# ProPrj_TweenWave_2025-12-02.net
KiCad netlist of a schematic drawn in EasyEDA Pro
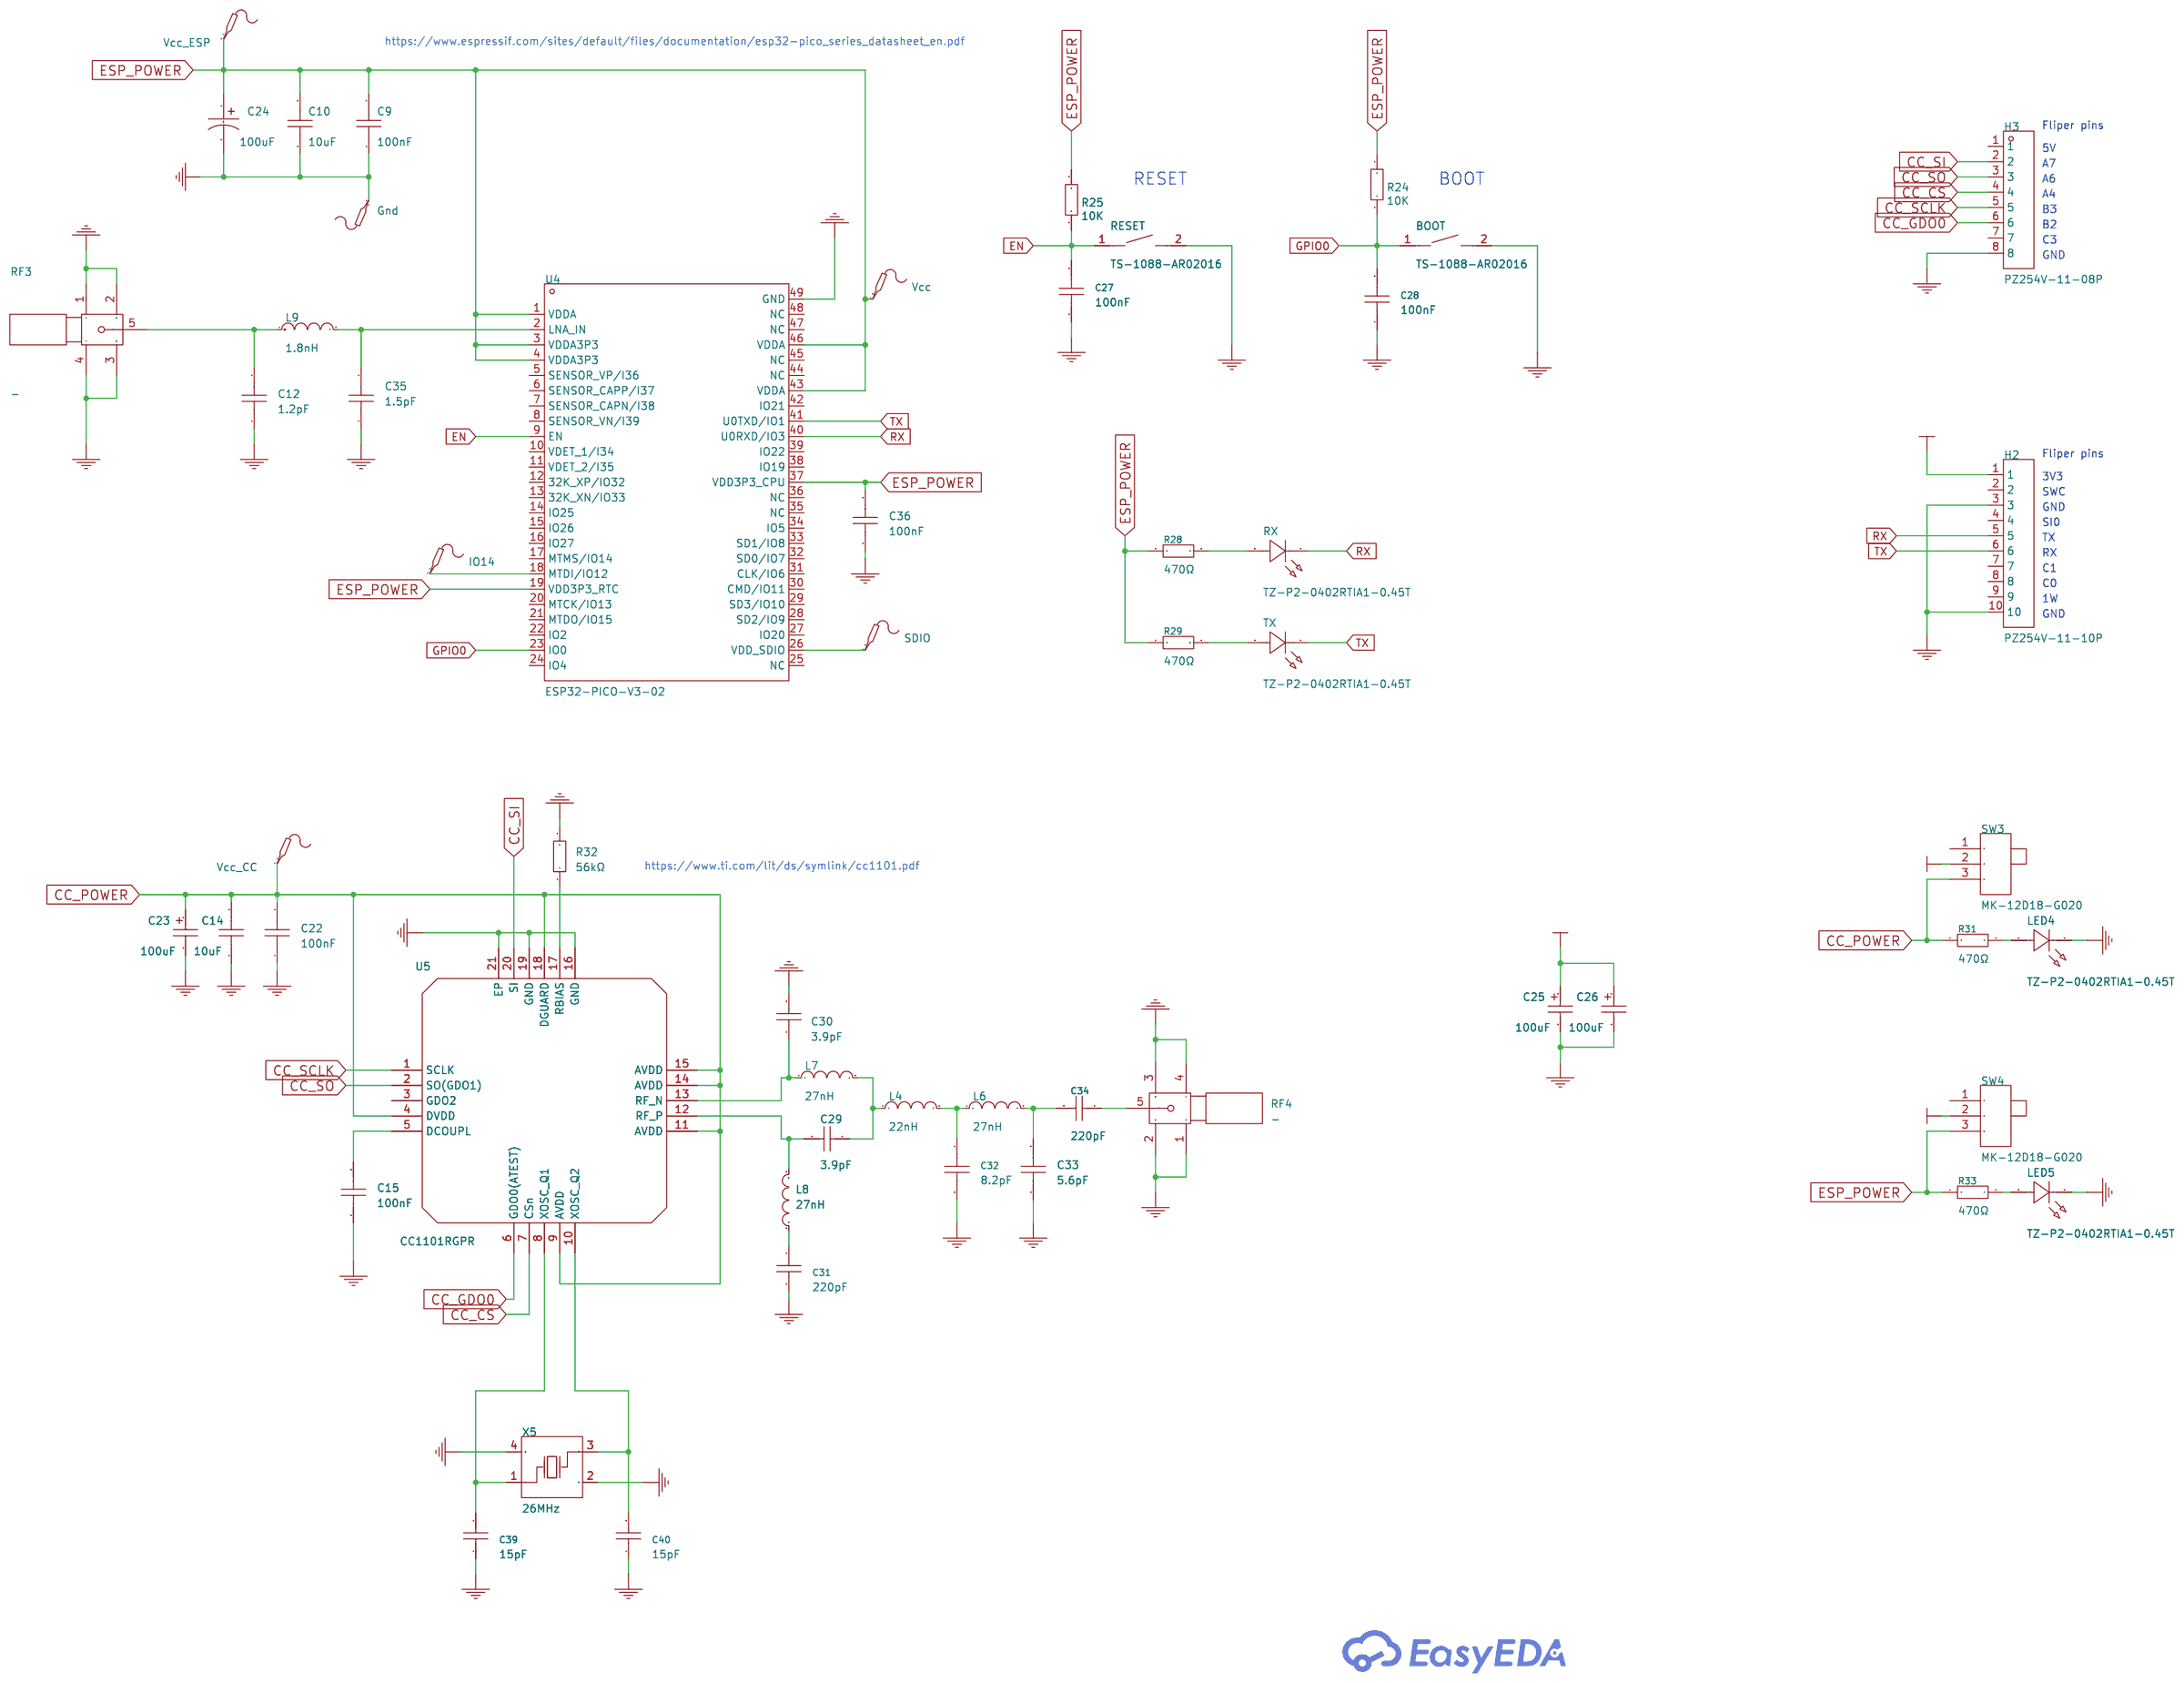
[diagram p0: schematic sheet]

(export (version "E")
  (design (tool "Eeschema 10.0.6"))
  (components
    (comp (ref "BOOT")
      (value "TS-1088-AR02016")
      (footprint "easyedapro:SW-SMD_L3.9-W3.0-P4.45")
      (fields (field (name "Manufacturer") "XUNPU(讯普)"))
      (libsource (lib "easyedapro") (part "TS-1088-AR02016"))
    )
    (comp (ref "C9")
      (value "100nF")
      (footprint "easyedapro:C0603")
      (description "Capacitance:100nF Tolerance:±10% Tolerance:±10% Voltage Rating:50V Temperature Coefficient:X7R")
      (fields
        (field (name "Manufacturer Part") "CC0603KRX7R9BB104")
        (field (name "Manufacturer") "YAGEO(国巨)")
      )
      (libsource (lib "easyedapro") (part "CC0603KRX7R9BB104"))
    )
    (comp (ref "C10")
      (value "10uF")
      (footprint "easyedapro:C0603")
      (fields
        (field (name "Manufacturer Part") "CL10A106MP8NNNC")
        (field (name "Manufacturer") "SAMSUNG(三星)")
      )
      (libsource (lib "easyedapro") (part "CL10A106MP8NNNC"))
    )
    (comp (ref "C12")
      (value "1.2pF")
      (footprint "easyedapro:C0201")
      (fields
        (field (name "Manufacturer Part") "GRM0335C1H1R2BA01D")
        (field (name "Manufacturer") "muRata(村田)")
      )
      (libsource (lib "easyedapro") (part "GRM0335C1H1R2BA01D"))
    )
    (comp (ref "C14")
      (value "10uF")
      (footprint "easyedapro:C0603")
      (fields
        (field (name "Manufacturer Part") "CL10A106MP8NNNC")
        (field (name "Manufacturer") "SAMSUNG(三星)")
      )
      (libsource (lib "easyedapro") (part "CL10A106MP8NNNC"))
    )
    (comp (ref "C15")
      (value "100nF")
      (footprint "easyedapro:C0603")
      (description "Capacitance:100nF Tolerance:±10% Tolerance:±10% Voltage Rating:50V Temperature Coefficient:X7R")
      (fields
        (field (name "Manufacturer Part") "CC0603KRX7R9BB104")
        (field (name "Manufacturer") "YAGEO(国巨)")
      )
      (libsource (lib "easyedapro") (part "CC0603KRX7R9BB104"))
    )
    (comp (ref "C22")
      (value "100nF")
      (footprint "easyedapro:C0603")
      (description "Capacitance:100nF Tolerance:±10% Tolerance:±10% Voltage Rating:50V Temperature Coefficient:X7R")
      (fields
        (field (name "Manufacturer Part") "CC0603KRX7R9BB104")
        (field (name "Manufacturer") "YAGEO(国巨)")
      )
      (libsource (lib "easyedapro") (part "CC0603KRX7R9BB104"))
    )
    (comp (ref "C23")
      (value "100uF")
      (footprint "easyedapro:CASE-B_3528")
      (fields (field (name "Manufacturer Part") "TAJB107K006RNJ") (field (name "Manufacturer") "Kyocera AVX"))
      (libsource (lib "easyedapro") (part "TAJB107K006RNJ"))
    )
    (comp (ref "C24")
      (value "100uF")
      (footprint "easyedapro:CASE-B_3528-1")
      (fields
        (field (name "Manufacturer Part") "TPSB107K006R0250")
        (field (name "Manufacturer") "Kyocera AVX")
      )
      (libsource (lib "easyedapro") (part "TPSB107K006R0250"))
    )
    (comp (ref "C25")
      (value "100uF")
      (footprint "easyedapro:CASE-B_3528")
      (fields (field (name "Manufacturer Part") "TAJB107K006RNJ") (field (name "Manufacturer") "Kyocera AVX"))
      (libsource (lib "easyedapro") (part "TAJB107K006RNJ"))
    )
    (comp (ref "C26")
      (value "100uF")
      (footprint "easyedapro:CASE-B_3528")
      (fields (field (name "Manufacturer Part") "TAJB107K006RNJ") (field (name "Manufacturer") "Kyocera AVX"))
      (libsource (lib "easyedapro") (part "TAJB107K006RNJ"))
    )
    (comp (ref "C27")
      (value "100nF")
      (footprint "easyedapro:C0402")
      (fields
        (field (name "Manufacturer Part") "CC0402KRX7R7BB104")
        (field (name "Manufacturer") "YAGEO(国巨)")
      )
      (libsource (lib "easyedapro") (part "CC0402KRX7R7BB104"))
    )
    (comp (ref "C28")
      (value "100nF")
      (footprint "easyedapro:C0402")
      (fields
        (field (name "Manufacturer Part") "CC0402KRX7R7BB104")
        (field (name "Manufacturer") "YAGEO(国巨)")
      )
      (libsource (lib "easyedapro") (part "CC0402KRX7R7BB104"))
    )
    (comp (ref "C29")
      (value "3.9pF")
      (footprint "easyedapro:C0402")
      (fields (field (name "Manufacturer Part") "0402CG3R9C500NT") (field (name "Manufacturer") "FH(风华)"))
      (libsource (lib "easyedapro") (part "0402CG3R9C500NT"))
    )
    (comp (ref "C30")
      (value "3.9pF")
      (footprint "easyedapro:C0402")
      (fields (field (name "Manufacturer Part") "0402CG3R9C500NT") (field (name "Manufacturer") "FH(风华)"))
      (libsource (lib "easyedapro") (part "0402CG3R9C500NT"))
    )
    (comp (ref "C31")
      (value "220pF")
      (footprint "easyedapro:C0402")
      (description "Capacitance:220pF Tolerance:±5% Tolerance:±5% Voltage Rating:50V Temperature Coefficient:NP0")
      (fields
        (field (name "Manufacturer Part") "CC0402JRNPO9BN221")
        (field (name "Manufacturer") "YAGEO(国巨)")
      )
      (libsource (lib "easyedapro") (part "CC0402JRNPO9BN221"))
    )
    (comp (ref "C32")
      (value "8.2pF")
      (footprint "easyedapro:C0402")
      (fields
        (field (name "Manufacturer Part") "CC0402BRNPO9BN8R2")
        (field (name "Manufacturer") "YAGEO(国巨)")
      )
      (libsource (lib "easyedapro") (part "CC0402BRNPO9BN8R2"))
    )
    (comp (ref "C33")
      (value "5.6pF")
      (footprint "easyedapro:C0402")
      (fields
        (field (name "Manufacturer Part") "CC0402BRNPO9BN5R6")
        (field (name "Manufacturer") "YAGEO(国巨)")
      )
      (libsource (lib "easyedapro") (part "CC0402BRNPO9BN5R6"))
    )
    (comp (ref "C34")
      (value "220pF")
      (footprint "easyedapro:C0402")
      (description "Capacitance:220pF Tolerance:±5% Tolerance:±5% Voltage Rating:50V Temperature Coefficient:NP0")
      (fields
        (field (name "Manufacturer Part") "CC0402JRNPO9BN221")
        (field (name "Manufacturer") "YAGEO(国巨)")
      )
      (libsource (lib "easyedapro") (part "CC0402JRNPO9BN221"))
    )
    (comp (ref "C35")
      (value "1.5pF")
      (footprint "easyedapro:C0201")
      (fields
        (field (name "Manufacturer Part") "GRM0335C1H1R5BA01D")
        (field (name "Manufacturer") "muRata(村田)")
      )
      (libsource (lib "easyedapro") (part "GRM0335C1H1R5BA01D"))
    )
    (comp (ref "C36")
      (value "100nF")
      (footprint "easyedapro:C0603")
      (description "Capacitance:100nF Tolerance:±10% Tolerance:±10% Voltage Rating:50V Temperature Coefficient:X7R")
      (fields
        (field (name "Manufacturer Part") "CC0603KRX7R9BB104")
        (field (name "Manufacturer") "YAGEO(国巨)")
      )
      (libsource (lib "easyedapro") (part "CC0603KRX7R9BB104"))
    )
    (comp (ref "C39")
      (value "15pF")
      (footprint "easyedapro:C0402")
      (fields
        (field (name "Manufacturer Part") "CC0402JRNPO9BN150")
        (field (name "Manufacturer") "YAGEO(国巨)")
      )
      (libsource (lib "easyedapro") (part "CC0402JRNPO9BN150"))
    )
    (comp (ref "C40")
      (value "15pF")
      (footprint "easyedapro:C0402")
      (fields
        (field (name "Manufacturer Part") "CC0402JRNPO9BN150")
        (field (name "Manufacturer") "YAGEO(国巨)")
      )
      (libsource (lib "easyedapro") (part "CC0402JRNPO9BN150"))
    )
    (comp (ref "Gnd")
      (value "~")
      (footprint "easyedapro:Test-Point-0.5mm")
      (description "Test Point 测试点")
      (libsource (lib "easyedapro") (part "Test-Point"))
    )
    (comp (ref "H2")
      (value "PZ254V-11-10P")
      (footprint "easyedapro:HDR-TH_10P-P2.54-V-M")
      (fields (field (name "Manufacturer") "XFCN(兴飞)"))
      (libsource (lib "easyedapro") (part "PZ254V-11-10P"))
    )
    (comp (ref "H3")
      (value "PZ254V-11-08P")
      (footprint "easyedapro:HDR-TH_8P-P2.54-V-M")
      (fields (field (name "Manufacturer") "XFCN(兴飞)"))
      (libsource (lib "easyedapro") (part "PZ254V-11-08P"))
    )
    (comp (ref "IO14")
      (value "~")
      (footprint "easyedapro:Test-Point-0.5mm")
      (description "Test Point 测试点")
      (libsource (lib "easyedapro") (part "Test-Point"))
    )
    (comp (ref "L4")
      (value "22nH")
      (footprint "easyedapro:L0402")
      (fields (field (name "Manufacturer Part") "LQG15HS22NJ02D") (field (name "Manufacturer") "muRata(村田)"))
      (libsource (lib "easyedapro") (part "LQG15HS22NJ02D"))
    )
    (comp (ref "L6")
      (value "27nH")
      (footprint "easyedapro:L0402-RD")
      (fields (field (name "Manufacturer Part") "LQG15HS27NJ02D") (field (name "Manufacturer") "muRata(村田)"))
      (libsource (lib "easyedapro") (part "LQG15HS27NJ02D"))
    )
    (comp (ref "L7")
      (value "27nH")
      (footprint "easyedapro:L0402-RD")
      (fields (field (name "Manufacturer Part") "LQG15HS27NJ02D") (field (name "Manufacturer") "muRata(村田)"))
      (libsource (lib "easyedapro") (part "LQG15HS27NJ02D"))
    )
    (comp (ref "L8")
      (value "27nH")
      (footprint "easyedapro:L0402-RD")
      (fields (field (name "Manufacturer Part") "LQG15HS27NJ02D") (field (name "Manufacturer") "muRata(村田)"))
      (libsource (lib "easyedapro") (part "LQG15HS27NJ02D"))
    )
    (comp (ref "L9")
      (value "1.8nH")
      (footprint "easyedapro:L0201-RD")
      (fields (field (name "Manufacturer Part") "LQP03TN1N8B02D") (field (name "Manufacturer") "muRata(村田)"))
      (libsource (lib "easyedapro") (part "LQP03TN1N8B02D"))
    )
    (comp (ref "LED4")
      (value "TZ-P2-0402RTIA1-0.45T")
      (footprint "easyedapro:LED0402-RD_RED")
      (fields (field (name "Manufacturer") "TUOZHAN(拓展光电)"))
      (libsource (lib "easyedapro") (part "TZ-P2-0402RTIA1-0.45T"))
    )
    (comp (ref "LED5")
      (value "TZ-P2-0402RTIA1-0.45T")
      (footprint "easyedapro:LED0402-RD_RED")
      (fields (field (name "Manufacturer") "TUOZHAN(拓展光电)"))
      (libsource (lib "easyedapro") (part "TZ-P2-0402RTIA1-0.45T"))
    )
    (comp (ref "R24")
      (value "10K")
      (footprint "easyedapro:R0603")
      (fields (field (name "Manufacturer Part") "RC0603DR-0710KL") (field (name "Manufacturer") "YAGEO(国巨)"))
      (libsource (lib "easyedapro") (part "10K"))
    )
    (comp (ref "R25")
      (value "10K")
      (footprint "easyedapro:R0603")
      (fields (field (name "Manufacturer Part") "RC0603DR-0710KL") (field (name "Manufacturer") "YAGEO(国巨)"))
      (libsource (lib "easyedapro") (part "10K"))
    )
    (comp (ref "R28")
      (value "470Ω")
      (footprint "easyedapro:R0402")
      (fields
        (field (name "Manufacturer Part") "0402WGF4700TCE")
        (field (name "Manufacturer") "UNI-ROYAL(厚声)")
      )
      (libsource (lib "easyedapro") (part "0402WGF4700TCE"))
    )
    (comp (ref "R29")
      (value "470Ω")
      (footprint "easyedapro:R0402")
      (fields
        (field (name "Manufacturer Part") "0402WGF4700TCE")
        (field (name "Manufacturer") "UNI-ROYAL(厚声)")
      )
      (libsource (lib "easyedapro") (part "0402WGF4700TCE"))
    )
    (comp (ref "R31")
      (value "470Ω")
      (footprint "easyedapro:R0402")
      (fields
        (field (name "Manufacturer Part") "0402WGF4700TCE")
        (field (name "Manufacturer") "UNI-ROYAL(厚声)")
      )
      (libsource (lib "easyedapro") (part "0402WGF4700TCE"))
    )
    (comp (ref "R32")
      (value "56kΩ")
      (footprint "easyedapro:R0402")
      (fields
        (field (name "Manufacturer Part") "0402WGF5602TCE")
        (field (name "Manufacturer") "UNI-ROYAL(厚声)")
      )
      (libsource (lib "easyedapro") (part "0402WGF5602TCE"))
    )
    (comp (ref "R33")
      (value "470Ω")
      (footprint "easyedapro:R0402")
      (fields
        (field (name "Manufacturer Part") "0402WGF4700TCE")
        (field (name "Manufacturer") "UNI-ROYAL(厚声)")
      )
      (libsource (lib "easyedapro") (part "0402WGF4700TCE"))
    )
    (comp (ref "RESET")
      (value "TS-1088-AR02016")
      (footprint "easyedapro:SW-SMD_L3.9-W3.0-P4.45")
      (fields (field (name "Manufacturer") "XUNPU(讯普)"))
      (libsource (lib "easyedapro") (part "TS-1088-AR02016"))
    )
    (comp (ref "RF3")
      (value "-")
      (footprint "easyedapro:SMA-SMD_BWSMA-KE-P001")
      (fields
        (field (name "Manufacturer Part") "BWSMA-KE-P001")
        (field (name "Manufacturer") "BAT WIRELESS(蝙蝠无线)")
      )
      (libsource (lib "easyedapro") (part "BWSMA-KE-P001"))
    )
    (comp (ref "RF4")
      (value "-")
      (footprint "easyedapro:SMA-SMD_BWSMA-KE-P001")
      (fields
        (field (name "Manufacturer Part") "BWSMA-KE-P001")
        (field (name "Manufacturer") "BAT WIRELESS(蝙蝠无线)")
      )
      (libsource (lib "easyedapro") (part "BWSMA-KE-P001"))
    )
    (comp (ref "RX")
      (value "TZ-P2-0402RTIA1-0.45T")
      (footprint "easyedapro:LED0402-RD_RED")
      (fields (field (name "Manufacturer") "TUOZHAN(拓展光电)"))
      (libsource (lib "easyedapro") (part "TZ-P2-0402RTIA1-0.45T"))
    )
    (comp (ref "SDIO")
      (value "~")
      (footprint "easyedapro:Test-Point-0.5mm")
      (description "Test Point 测试点")
      (libsource (lib "easyedapro") (part "Test-Point"))
    )
    (comp (ref "SW3")
      (value "MK-12D18-G020")
      (footprint "easyedapro:SW-TH_MK-12D18-G040")
      (fields (field (name "Manufacturer") "G-Switch(品赞)"))
      (libsource (lib "easyedapro") (part "MK-12D18-G020"))
    )
    (comp (ref "SW4")
      (value "MK-12D18-G020")
      (footprint "easyedapro:SW-TH_MK-12D18-G040")
      (fields (field (name "Manufacturer") "G-Switch(品赞)"))
      (libsource (lib "easyedapro") (part "MK-12D18-G020"))
    )
    (comp (ref "TX")
      (value "TZ-P2-0402RTIA1-0.45T")
      (footprint "easyedapro:LED0402-RD_RED")
      (fields (field (name "Manufacturer") "TUOZHAN(拓展光电)"))
      (libsource (lib "easyedapro") (part "TZ-P2-0402RTIA1-0.45T"))
    )
    (comp (ref "U4")
      (value "ESP32-PICO-V3-02")
      (footprint "easyedapro:QFN-48_L7.0-W7.0-P0.50-BL-EP5.1")
      (fields (field (name "Manufacturer") "ESPRESSIF(乐鑫)"))
      (libsource (lib "easyedapro") (part "ESP32-PICO-V3-02"))
    )
    (comp (ref "U5")
      (value "CC1101RGPR")
      (footprint "easyedapro:QFN-20_L4.0-W4.0-P0.5-TL-EP")
      (fields (field (name "Manufacturer") "TI(德州仪器)"))
      (libsource (lib "easyedapro") (part "CC1101RGPR"))
    )
    (comp (ref "Vcc")
      (value "~")
      (footprint "easyedapro:Test-Point-0.5mm")
      (description "Test Point 测试点")
      (libsource (lib "easyedapro") (part "Test-Point"))
    )
    (comp (ref "Vcc_CC")
      (value "~")
      (footprint "easyedapro:Test-Point-0.5mm")
      (description "Test Point 测试点")
      (libsource (lib "easyedapro") (part "Test-Point"))
    )
    (comp (ref "Vcc_ESP")
      (value "~")
      (footprint "easyedapro:Test-Point-0.5mm")
      (description "Test Point 测试点")
      (libsource (lib "easyedapro") (part "Test-Point"))
    )
    (comp (ref "X5")
      (value "26MHz")
      (footprint "easyedapro:CRYSTAL-SMD_4P-L3.2-W2.5-BL")
      (fields (field (name "Manufacturer Part") "X322526MMB4SI") (field (name "Manufacturer") "YXC(扬兴晶振)"))
      (libsource (lib "easyedapro") (part "X322526MMB4SI"))
    )
  )
  (nets
    (net (code "1") (name "3V3") (class "Default")
      (node (ref "C25") (pin "1") (pinfunction "1_1") (pintype "input"))
      (node (ref "C26") (pin "1") (pinfunction "1_1") (pintype "input"))
      (node (ref "H2") (pin "1") (pinfunction "1_1") (pintype "unspecified"))
      (node (ref "SW3") (pin "2") (pinfunction "2_2") (pintype "unspecified"))
      (node (ref "SW4") (pin "2") (pinfunction "2_2") (pintype "unspecified"))
    )
    (net (code "2") (name "CC_CS") (class "Default")
      (node (ref "H3") (pin "4") (pinfunction "4_4") (pintype "unspecified"))
      (node (ref "U5") (pin "7") (pinfunction "CSn_7") (pintype "unspecified"))
    )
    (net (code "3") (name "CC_GDO0") (class "Default")
      (node (ref "H3") (pin "6") (pinfunction "6_6") (pintype "unspecified"))
      (node (ref "U5") (pin "6") (pinfunction "GDO0(ATEST)_6") (pintype "unspecified"))
    )
    (net (code "4") (name "CC_POWER") (class "Default")
      (node (ref "C14") (pin "2") (pinfunction "2_2") (pintype "unspecified"))
      (node (ref "C22") (pin "2") (pinfunction "2_2") (pintype "unspecified"))
      (node (ref "C23") (pin "1") (pinfunction "1_1") (pintype "input"))
      (node (ref "R31") (pin "1") (pinfunction "1_1") (pintype "input"))
      (node (ref "SW3") (pin "3") (pinfunction "3_3") (pintype "unspecified"))
      (node (ref "U5") (pin "11") (pinfunction "AVDD_11") (pintype "unspecified"))
      (node (ref "U5") (pin "14") (pinfunction "AVDD_14") (pintype "unspecified"))
      (node (ref "U5") (pin "15") (pinfunction "AVDD_15") (pintype "unspecified"))
      (node (ref "U5") (pin "18") (pinfunction "DGUARD_18") (pintype "unspecified"))
      (node (ref "U5") (pin "4") (pinfunction "DVDD_4") (pintype "unspecified"))
      (node (ref "U5") (pin "9") (pinfunction "AVDD_9") (pintype "unspecified"))
      (node (ref "Vcc_CC") (pin "1") (pinfunction "1_1") (pintype "unspecified"))
    )
    (net (code "5") (name "CC_SCLK") (class "Default")
      (node (ref "H3") (pin "5") (pinfunction "5_5") (pintype "unspecified"))
      (node (ref "U5") (pin "1") (pinfunction "SCLK_1") (pintype "unspecified"))
    )
    (net (code "6") (name "CC_SI") (class "Default")
      (node (ref "H3") (pin "2") (pinfunction "2_2") (pintype "unspecified"))
      (node (ref "U5") (pin "20") (pinfunction "SI_20") (pintype "unspecified"))
    )
    (net (code "7") (name "CC_SO") (class "Default")
      (node (ref "H3") (pin "3") (pinfunction "3_3") (pintype "unspecified"))
      (node (ref "U5") (pin "2") (pinfunction "SO(GDO1)_2") (pintype "unspecified"))
    )
    (net (code "8") (name "EN") (class "Default")
      (node (ref "C27") (pin "2") (pinfunction "2_2") (pintype "input"))
      (node (ref "R25") (pin "1") (pinfunction "1_1") (pintype "input"))
      (node (ref "RESET") (pin "1") (pinfunction "1_1") (pintype "unspecified"))
      (node (ref "U4") (pin "9") (pinfunction "EN_9") (pintype "unspecified"))
    )
    (net (code "9") (name "ESP_POWER") (class "Default")
      (node (ref "C10") (pin "2") (pinfunction "2_2") (pintype "unspecified"))
      (node (ref "C24") (pin "1") (pinfunction "1_1") (pintype "unspecified"))
      (node (ref "C36") (pin "2") (pinfunction "2_2") (pintype "unspecified"))
      (node (ref "C9") (pin "2") (pinfunction "2_2") (pintype "unspecified"))
      (node (ref "R24") (pin "2") (pinfunction "2_2") (pintype "input"))
      (node (ref "R25") (pin "2") (pinfunction "2_2") (pintype "input"))
      (node (ref "R28") (pin "1") (pinfunction "1_1") (pintype "input"))
      (node (ref "R29") (pin "1") (pinfunction "1_1") (pintype "input"))
      (node (ref "R33") (pin "1") (pinfunction "1_1") (pintype "input"))
      (node (ref "SW4") (pin "3") (pinfunction "3_3") (pintype "unspecified"))
      (node (ref "U4") (pin "1") (pinfunction "VDDA_1") (pintype "unspecified"))
      (node (ref "U4") (pin "19") (pinfunction "VDD3P3_RTC_19") (pintype "unspecified"))
      (node (ref "U4") (pin "3") (pinfunction "VDDA3P3_3") (pintype "unspecified"))
      (node (ref "U4") (pin "37") (pinfunction "VDD3P3_CPU_37") (pintype "unspecified"))
      (node (ref "U4") (pin "4") (pinfunction "VDDA3P3_4") (pintype "unspecified"))
      (node (ref "U4") (pin "43") (pinfunction "VDDA_43") (pintype "unspecified"))
      (node (ref "U4") (pin "46") (pinfunction "VDDA_46") (pintype "unspecified"))
      (node (ref "Vcc") (pin "1") (pinfunction "1_1") (pintype "unspecified"))
      (node (ref "Vcc_ESP") (pin "1") (pinfunction "1_1") (pintype "unspecified"))
    )
    (net (code "10") (name "GND") (class "Default")
      (node (ref "BOOT") (pin "2") (pinfunction "2_2") (pintype "unspecified"))
      (node (ref "C10") (pin "1") (pinfunction "1_1") (pintype "unspecified"))
      (node (ref "C12") (pin "1") (pinfunction "1_1") (pintype "unspecified"))
      (node (ref "C14") (pin "1") (pinfunction "1_1") (pintype "unspecified"))
      (node (ref "C15") (pin "1") (pinfunction "1_1") (pintype "unspecified"))
      (node (ref "C22") (pin "1") (pinfunction "1_1") (pintype "unspecified"))
      (node (ref "C23") (pin "2") (pinfunction "2_2") (pintype "input"))
      (node (ref "C24") (pin "2") (pinfunction "2_2") (pintype "unspecified"))
      (node (ref "C25") (pin "2") (pinfunction "2_2") (pintype "input"))
      (node (ref "C26") (pin "2") (pinfunction "2_2") (pintype "input"))
      (node (ref "C27") (pin "1") (pinfunction "1_1") (pintype "input"))
      (node (ref "C28") (pin "1") (pinfunction "1_1") (pintype "input"))
      (node (ref "C30") (pin "2") (pinfunction "2_2") (pintype "input"))
      (node (ref "C31") (pin "1") (pinfunction "1_1") (pintype "input"))
      (node (ref "C32") (pin "2") (pinfunction "2_2") (pintype "input"))
      (node (ref "C33") (pin "1") (pinfunction "1_1") (pintype "unspecified"))
      (node (ref "C35") (pin "1") (pinfunction "1_1") (pintype "unspecified"))
      (node (ref "C36") (pin "1") (pinfunction "1_1") (pintype "unspecified"))
      (node (ref "C39") (pin "1") (pinfunction "1_1") (pintype "input"))
      (node (ref "C40") (pin "1") (pinfunction "1_1") (pintype "input"))
      (node (ref "C9") (pin "1") (pinfunction "1_1") (pintype "unspecified"))
      (node (ref "Gnd") (pin "1") (pinfunction "1_1") (pintype "unspecified"))
      (node (ref "H2") (pin "10") (pinfunction "10_10") (pintype "unspecified"))
      (node (ref "H2") (pin "3") (pinfunction "3_3") (pintype "unspecified"))
      (node (ref "H3") (pin "8") (pinfunction "8_8") (pintype "unspecified"))
      (node (ref "LED4") (pin "1") (pinfunction "K_1") (pintype "unspecified"))
      (node (ref "LED5") (pin "1") (pinfunction "K_1") (pintype "unspecified"))
      (node (ref "R32") (pin "2") (pinfunction "2_2") (pintype "input"))
      (node (ref "RESET") (pin "2") (pinfunction "2_2") (pintype "unspecified"))
      (node (ref "RF3") (pin "1") (pinfunction "1_1") (pintype "unspecified"))
      (node (ref "RF3") (pin "2") (pinfunction "2_2") (pintype "unspecified"))
      (node (ref "RF3") (pin "3") (pinfunction "3_3") (pintype "unspecified"))
      (node (ref "RF3") (pin "4") (pinfunction "4_4") (pintype "unspecified"))
      (node (ref "RF4") (pin "1") (pinfunction "1_1") (pintype "unspecified"))
      (node (ref "RF4") (pin "2") (pinfunction "2_2") (pintype "unspecified"))
      (node (ref "RF4") (pin "3") (pinfunction "3_3") (pintype "unspecified"))
      (node (ref "RF4") (pin "4") (pinfunction "4_4") (pintype "unspecified"))
      (node (ref "U4") (pin "49") (pinfunction "GND_49") (pintype "unspecified"))
      (node (ref "U5") (pin "16") (pinfunction "GND_16") (pintype "unspecified"))
      (node (ref "U5") (pin "19") (pinfunction "GND_19") (pintype "unspecified"))
      (node (ref "U5") (pin "21") (pinfunction "EP_21") (pintype "unspecified"))
      (node (ref "X5") (pin "2") (pinfunction "GND_2") (pintype "unspecified"))
      (node (ref "X5") (pin "4") (pinfunction "GND_4") (pintype "unspecified"))
    )
    (net (code "11") (name "GPIO0") (class "Default")
      (node (ref "BOOT") (pin "1") (pinfunction "1_1") (pintype "unspecified"))
      (node (ref "C28") (pin "2") (pinfunction "2_2") (pintype "input"))
      (node (ref "R24") (pin "1") (pinfunction "1_1") (pintype "input"))
      (node (ref "U4") (pin "23") (pinfunction "IO0_23") (pintype "unspecified"))
    )
    (net (code "12") (name "Net-(C12-Pad2)") (class "Default")
      (node (ref "C12") (pin "2") (pinfunction "2_2") (pintype "unspecified"))
      (node (ref "L9") (pin "1") (pinfunction "1_1") (pintype "input"))
      (node (ref "RF3") (pin "5") (pinfunction "5_5") (pintype "unspecified"))
    )
    (net (code "13") (name "Net-(C29-Pad2)") (class "Default")
      (node (ref "C29") (pin "2") (pinfunction "2_2") (pintype "input"))
      (node (ref "L4") (pin "1") (pinfunction "1_1") (pintype "unspecified"))
      (node (ref "L7") (pin "2") (pinfunction "2_2") (pintype "unspecified"))
    )
    (net (code "14") (name "Net-(C31-Pad2)") (class "Default")
      (node (ref "C31") (pin "2") (pinfunction "2_2") (pintype "input"))
      (node (ref "L8") (pin "1") (pinfunction "1_1") (pintype "unspecified"))
    )
    (net (code "15") (name "Net-(C32-Pad1)") (class "Default")
      (node (ref "C32") (pin "1") (pinfunction "1_1") (pintype "input"))
      (node (ref "L4") (pin "2") (pinfunction "2_2") (pintype "unspecified"))
      (node (ref "L6") (pin "1") (pinfunction "1_1") (pintype "unspecified"))
    )
    (net (code "16") (name "Net-(C33-Pad2)") (class "Default")
      (node (ref "C33") (pin "2") (pinfunction "2_2") (pintype "unspecified"))
      (node (ref "C34") (pin "2") (pinfunction "2_2") (pintype "input"))
      (node (ref "L6") (pin "2") (pinfunction "2_2") (pintype "unspecified"))
    )
    (net (code "17") (name "Net-(C34-Pad1)") (class "Default")
      (node (ref "C34") (pin "1") (pinfunction "1_1") (pintype "input"))
      (node (ref "RF4") (pin "5") (pinfunction "5_5") (pintype "unspecified"))
    )
    (net (code "18") (name "Net-(LED4-A)") (class "Default")
      (node (ref "LED4") (pin "2") (pinfunction "A_2") (pintype "unspecified"))
      (node (ref "R31") (pin "2") (pinfunction "2_2") (pintype "input"))
    )
    (net (code "19") (name "Net-(LED5-A)") (class "Default")
      (node (ref "LED5") (pin "2") (pinfunction "A_2") (pintype "unspecified"))
      (node (ref "R33") (pin "2") (pinfunction "2_2") (pintype "input"))
    )
    (net (code "20") (name "Net-(RX-A)") (class "Default")
      (node (ref "R28") (pin "2") (pinfunction "2_2") (pintype "input"))
      (node (ref "RX") (pin "2") (pinfunction "A_2") (pintype "unspecified"))
    )
    (net (code "21") (name "Net-(TX-A)") (class "Default")
      (node (ref "R29") (pin "2") (pinfunction "2_2") (pintype "input"))
      (node (ref "TX") (pin "2") (pinfunction "A_2") (pintype "unspecified"))
    )
    (net (code "22") (name "Net-(U4-LNA_IN)") (class "Default")
      (node (ref "C35") (pin "2") (pinfunction "2_2") (pintype "unspecified"))
      (node (ref "L9") (pin "2") (pinfunction "2_2") (pintype "input"))
      (node (ref "U4") (pin "2") (pinfunction "LNA_IN_2") (pintype "unspecified"))
    )
    (net (code "23") (name "Net-(U4-MTDI{slash}IO12)") (class "Default")
      (node (ref "IO14") (pin "1") (pinfunction "1_1") (pintype "unspecified"))
      (node (ref "U4") (pin "18") (pinfunction "MTDI/IO12_18") (pintype "unspecified"))
    )
    (net (code "24") (name "Net-(U4-VDD_SDIO)") (class "Default")
      (node (ref "SDIO") (pin "1") (pinfunction "1_1") (pintype "unspecified"))
      (node (ref "U4") (pin "26") (pinfunction "VDD_SDIO_26") (pintype "unspecified"))
    )
    (net (code "25") (name "Net-(U5-DCOUPL)") (class "Default")
      (node (ref "C15") (pin "2") (pinfunction "2_2") (pintype "unspecified"))
      (node (ref "U5") (pin "5") (pinfunction "DCOUPL_5") (pintype "unspecified"))
    )
    (net (code "26") (name "Net-(U5-RBIAS)") (class "Default")
      (node (ref "R32") (pin "1") (pinfunction "1_1") (pintype "input"))
      (node (ref "U5") (pin "17") (pinfunction "RBIAS_17") (pintype "unspecified"))
    )
    (net (code "27") (name "Net-(U5-RF_N)") (class "Default")
      (node (ref "C30") (pin "1") (pinfunction "1_1") (pintype "input"))
      (node (ref "L7") (pin "1") (pinfunction "1_1") (pintype "unspecified"))
      (node (ref "U5") (pin "13") (pinfunction "RF_N_13") (pintype "unspecified"))
    )
    (net (code "28") (name "Net-(U5-RF_P)") (class "Default")
      (node (ref "C29") (pin "1") (pinfunction "1_1") (pintype "input"))
      (node (ref "L8") (pin "2") (pinfunction "2_2") (pintype "unspecified"))
      (node (ref "U5") (pin "12") (pinfunction "RF_P_12") (pintype "unspecified"))
    )
    (net (code "29") (name "Net-(U5-XOSC_Q1)") (class "Default")
      (node (ref "C39") (pin "2") (pinfunction "2_2") (pintype "input"))
      (node (ref "U5") (pin "8") (pinfunction "XOSC_Q1_8") (pintype "unspecified"))
      (node (ref "X5") (pin "1") (pinfunction "OSC1_1") (pintype "unspecified"))
    )
    (net (code "30") (name "Net-(U5-XOSC_Q2)") (class "Default")
      (node (ref "C40") (pin "2") (pinfunction "2_2") (pintype "input"))
      (node (ref "U5") (pin "10") (pinfunction "XOSC_Q2_10") (pintype "unspecified"))
      (node (ref "X5") (pin "3") (pinfunction "OSC2_3") (pintype "unspecified"))
    )
    (net (code "31") (name "RX") (class "Default")
      (node (ref "H2") (pin "5") (pinfunction "5_5") (pintype "unspecified"))
      (node (ref "RX") (pin "1") (pinfunction "K_1") (pintype "unspecified"))
      (node (ref "U4") (pin "40") (pinfunction "U0RXD/IO3_40") (pintype "unspecified"))
    )
    (net (code "32") (name "TX") (class "Default")
      (node (ref "H2") (pin "6") (pinfunction "6_6") (pintype "unspecified"))
      (node (ref "TX") (pin "1") (pinfunction "K_1") (pintype "unspecified"))
      (node (ref "U4") (pin "41") (pinfunction "U0TXD/IO1_41") (pintype "unspecified"))
    )
    (net (code "33") (name "unconnected-(H2-Pad2)") (class "Default")
      (node (ref "H2") (pin "2") (pinfunction "2_2") (pintype "unspecified"))
    )
    (net (code "34") (name "unconnected-(H2-Pad4)") (class "Default")
      (node (ref "H2") (pin "4") (pinfunction "4_4") (pintype "unspecified"))
    )
    (net (code "35") (name "unconnected-(H2-Pad7)") (class "Default")
      (node (ref "H2") (pin "7") (pinfunction "7_7") (pintype "unspecified"))
    )
    (net (code "36") (name "unconnected-(H2-Pad8)") (class "Default")
      (node (ref "H2") (pin "8") (pinfunction "8_8") (pintype "unspecified"))
    )
    (net (code "37") (name "unconnected-(H2-Pad9)") (class "Default")
      (node (ref "H2") (pin "9") (pinfunction "9_9") (pintype "unspecified"))
    )
    (net (code "38") (name "unconnected-(H3-Pad1)") (class "Default")
      (node (ref "H3") (pin "1") (pinfunction "1_1") (pintype "unspecified"))
    )
    (net (code "39") (name "unconnected-(H3-Pad7)") (class "Default")
      (node (ref "H3") (pin "7") (pinfunction "7_7") (pintype "unspecified"))
    )
    (net (code "40") (name "unconnected-(SW3-Pad1)") (class "Default")
      (node (ref "SW3") (pin "1") (pinfunction "1_1") (pintype "unspecified"))
    )
    (net (code "41") (name "unconnected-(SW4-Pad1)") (class "Default")
      (node (ref "SW4") (pin "1") (pinfunction "1_1") (pintype "unspecified"))
    )
    (net (code "42") (name "unconnected-(U4-32K_XN{slash}IO33-Pad13)") (class "Default")
      (node (ref "U4") (pin "13") (pinfunction "32K_XN/IO33_13") (pintype "unspecified"))
    )
    (net (code "43") (name "unconnected-(U4-32K_XP{slash}IO32-Pad12)") (class "Default")
      (node (ref "U4") (pin "12") (pinfunction "32K_XP/IO32_12") (pintype "unspecified"))
    )
    (net (code "44") (name "unconnected-(U4-CLK{slash}IO6-Pad31)") (class "Default")
      (node (ref "U4") (pin "31") (pinfunction "CLK/IO6_31") (pintype "unspecified"))
    )
    (net (code "45") (name "unconnected-(U4-CMD{slash}IO11-Pad30)") (class "Default")
      (node (ref "U4") (pin "30") (pinfunction "CMD/IO11_30") (pintype "unspecified"))
    )
    (net (code "46") (name "unconnected-(U4-IO2-Pad22)") (class "Default")
      (node (ref "U4") (pin "22") (pinfunction "IO2_22") (pintype "unspecified"))
    )
    (net (code "47") (name "unconnected-(U4-IO4-Pad24)") (class "Default")
      (node (ref "U4") (pin "24") (pinfunction "IO4_24") (pintype "unspecified"))
    )
    (net (code "48") (name "unconnected-(U4-IO5-Pad34)") (class "Default")
      (node (ref "U4") (pin "34") (pinfunction "IO5_34") (pintype "unspecified"))
    )
    (net (code "49") (name "unconnected-(U4-IO19-Pad38)") (class "Default")
      (node (ref "U4") (pin "38") (pinfunction "IO19_38") (pintype "unspecified"))
    )
    (net (code "50") (name "unconnected-(U4-IO20-Pad27)") (class "Default")
      (node (ref "U4") (pin "27") (pinfunction "IO20_27") (pintype "unspecified"))
    )
    (net (code "51") (name "unconnected-(U4-IO21-Pad42)") (class "Default")
      (node (ref "U4") (pin "42") (pinfunction "IO21_42") (pintype "unspecified"))
    )
    (net (code "52") (name "unconnected-(U4-IO22-Pad39)") (class "Default")
      (node (ref "U4") (pin "39") (pinfunction "IO22_39") (pintype "unspecified"))
    )
    (net (code "53") (name "unconnected-(U4-IO25-Pad14)") (class "Default")
      (node (ref "U4") (pin "14") (pinfunction "IO25_14") (pintype "unspecified"))
    )
    (net (code "54") (name "unconnected-(U4-IO26-Pad15)") (class "Default")
      (node (ref "U4") (pin "15") (pinfunction "IO26_15") (pintype "unspecified"))
    )
    (net (code "55") (name "unconnected-(U4-IO27-Pad16)") (class "Default")
      (node (ref "U4") (pin "16") (pinfunction "IO27_16") (pintype "unspecified"))
    )
    (net (code "56") (name "unconnected-(U4-MTCK{slash}IO13-Pad20)") (class "Default")
      (node (ref "U4") (pin "20") (pinfunction "MTCK/IO13_20") (pintype "unspecified"))
    )
    (net (code "57") (name "unconnected-(U4-MTDO{slash}IO15-Pad21)") (class "Default")
      (node (ref "U4") (pin "21") (pinfunction "MTDO/IO15_21") (pintype "unspecified"))
    )
    (net (code "58") (name "unconnected-(U4-MTMS{slash}IO14-Pad17)") (class "Default")
      (node (ref "U4") (pin "17") (pinfunction "MTMS/IO14_17") (pintype "unspecified"))
    )
    (net (code "59") (name "unconnected-(U4-NC-Pad25)") (class "Default")
      (node (ref "U4") (pin "25") (pinfunction "NC_25") (pintype "unspecified"))
    )
    (net (code "60") (name "unconnected-(U4-NC-Pad35)") (class "Default")
      (node (ref "U4") (pin "35") (pinfunction "NC_35") (pintype "unspecified"))
    )
    (net (code "61") (name "unconnected-(U4-NC-Pad36)") (class "Default")
      (node (ref "U4") (pin "36") (pinfunction "NC_36") (pintype "unspecified"))
    )
    (net (code "62") (name "unconnected-(U4-NC-Pad44)") (class "Default")
      (node (ref "U4") (pin "44") (pinfunction "NC_44") (pintype "unspecified"))
    )
    (net (code "63") (name "unconnected-(U4-NC-Pad45)") (class "Default")
      (node (ref "U4") (pin "45") (pinfunction "NC_45") (pintype "unspecified"))
    )
    (net (code "64") (name "unconnected-(U4-NC-Pad47)") (class "Default")
      (node (ref "U4") (pin "47") (pinfunction "NC_47") (pintype "unspecified"))
    )
    (net (code "65") (name "unconnected-(U4-NC-Pad48)") (class "Default")
      (node (ref "U4") (pin "48") (pinfunction "NC_48") (pintype "unspecified"))
    )
    (net (code "66") (name "unconnected-(U4-SD0{slash}IO7-Pad32)") (class "Default")
      (node (ref "U4") (pin "32") (pinfunction "SD0/IO7_32") (pintype "unspecified"))
    )
    (net (code "67") (name "unconnected-(U4-SD1{slash}IO8-Pad33)") (class "Default")
      (node (ref "U4") (pin "33") (pinfunction "SD1/IO8_33") (pintype "unspecified"))
    )
    (net (code "68") (name "unconnected-(U4-SD2{slash}IO9-Pad28)") (class "Default")
      (node (ref "U4") (pin "28") (pinfunction "SD2/IO9_28") (pintype "unspecified"))
    )
    (net (code "69") (name "unconnected-(U4-SD3{slash}IO10-Pad29)") (class "Default")
      (node (ref "U4") (pin "29") (pinfunction "SD3/IO10_29") (pintype "unspecified"))
    )
    (net (code "70") (name "unconnected-(U4-SENSOR_CAPN{slash}I38-Pad7)") (class "Default")
      (node (ref "U4") (pin "7") (pinfunction "SENSOR_CAPN/I38_7") (pintype "unspecified"))
    )
    (net (code "71") (name "unconnected-(U4-SENSOR_CAPP{slash}I37-Pad6)") (class "Default")
      (node (ref "U4") (pin "6") (pinfunction "SENSOR_CAPP/I37_6") (pintype "unspecified"))
    )
    (net (code "72") (name "unconnected-(U4-SENSOR_VN{slash}I39-Pad8)") (class "Default")
      (node (ref "U4") (pin "8") (pinfunction "SENSOR_VN/I39_8") (pintype "unspecified"))
    )
    (net (code "73") (name "unconnected-(U4-SENSOR_VP{slash}I36-Pad5)") (class "Default")
      (node (ref "U4") (pin "5") (pinfunction "SENSOR_VP/I36_5") (pintype "unspecified"))
    )
    (net (code "74") (name "unconnected-(U4-VDET_1{slash}I34-Pad10)") (class "Default")
      (node (ref "U4") (pin "10") (pinfunction "VDET_1/I34_10") (pintype "unspecified"))
    )
    (net (code "75") (name "unconnected-(U4-VDET_2{slash}I35-Pad11)") (class "Default")
      (node (ref "U4") (pin "11") (pinfunction "VDET_2/I35_11") (pintype "unspecified"))
    )
    (net (code "76") (name "unconnected-(U5-GDO2-Pad3)") (class "Default")
      (node (ref "U5") (pin "3") (pinfunction "GDO2_3") (pintype "unspecified"))
    )
  )
)
